# magnets.net
KiCad netlist of a schematic drawn in Altium Designer
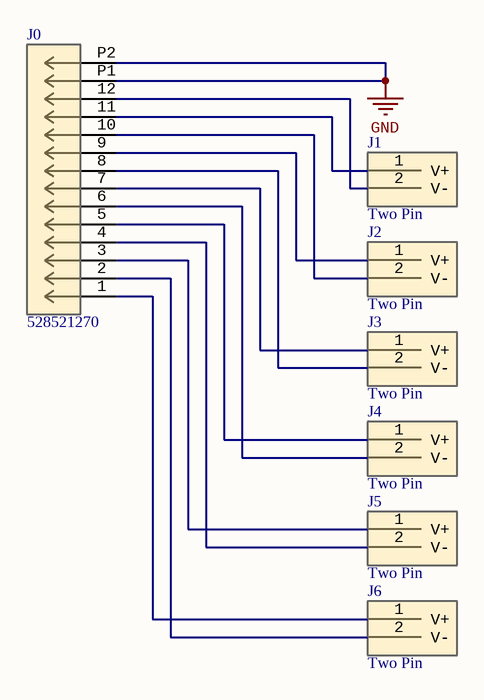
[diagram p0: magnets.SchDoc]

(export (version "E")
  (design (tool "Eeschema 10.0.6"))
  (components
    (comp (ref "J0")
      (value "528521270")
      (footprint "528521270:528521270")
      (fields (field (name "COPYRIGHT") "Copyright (C) 2025 Ultra Librarian. All rights reserved."))
      (libsource (lib "528521270") (part "528521270"))
    )
    (comp (ref "J1")
      (value "Two Pin")
      (footprint "twopin:TWO_PIN")
      (libsource (lib "twopin") (part "two_pin"))
    )
    (comp (ref "J2")
      (value "Two Pin")
      (footprint "twopin:TWO_PIN")
      (libsource (lib "twopin") (part "two_pin"))
    )
    (comp (ref "J3")
      (value "Two Pin")
      (footprint "twopin:TWO_PIN")
      (libsource (lib "twopin") (part "two_pin"))
    )
    (comp (ref "J4")
      (value "Two Pin")
      (footprint "twopin:TWO_PIN")
      (libsource (lib "twopin") (part "two_pin"))
    )
    (comp (ref "J5")
      (value "Two Pin")
      (footprint "twopin:TWO_PIN")
      (libsource (lib "twopin") (part "two_pin"))
    )
    (comp (ref "J6")
      (value "Two Pin")
      (footprint "twopin:TWO_PIN")
      (libsource (lib "twopin") (part "two_pin"))
    )
  )
  (nets
    (net (code "1") (name "GND") (class "Default")
      (node (ref "J0") (pin "P1") (pinfunction "P1_P1") (pintype "passive"))
      (node (ref "J0") (pin "P2") (pinfunction "P2_P2") (pintype "passive"))
    )
    (net (code "2") (name "Net-(J1-V+)") (class "Default")
      (node (ref "J0") (pin "11") (pinfunction "11_11") (pintype "passive"))
      (node (ref "J1") (pin "1") (pinfunction "V+_1") (pintype "passive"))
    )
    (net (code "3") (name "Net-(J1-V-)") (class "Default")
      (node (ref "J0") (pin "12") (pinfunction "12_12") (pintype "passive"))
      (node (ref "J1") (pin "2") (pinfunction "V-_2") (pintype "passive"))
    )
    (net (code "4") (name "Net-(J2-V+)") (class "Default")
      (node (ref "J0") (pin "9") (pinfunction "9_9") (pintype "passive"))
      (node (ref "J2") (pin "1") (pinfunction "V+_1") (pintype "passive"))
    )
    (net (code "5") (name "Net-(J2-V-)") (class "Default")
      (node (ref "J0") (pin "10") (pinfunction "10_10") (pintype "passive"))
      (node (ref "J2") (pin "2") (pinfunction "V-_2") (pintype "passive"))
    )
    (net (code "6") (name "Net-(J3-V+)") (class "Default")
      (node (ref "J0") (pin "7") (pinfunction "7_7") (pintype "passive"))
      (node (ref "J3") (pin "1") (pinfunction "V+_1") (pintype "passive"))
    )
    (net (code "7") (name "Net-(J3-V-)") (class "Default")
      (node (ref "J0") (pin "8") (pinfunction "8_8") (pintype "passive"))
      (node (ref "J3") (pin "2") (pinfunction "V-_2") (pintype "passive"))
    )
    (net (code "8") (name "Net-(J4-V+)") (class "Default")
      (node (ref "J0") (pin "5") (pinfunction "5_5") (pintype "passive"))
      (node (ref "J4") (pin "1") (pinfunction "V+_1") (pintype "passive"))
    )
    (net (code "9") (name "Net-(J4-V-)") (class "Default")
      (node (ref "J0") (pin "6") (pinfunction "6_6") (pintype "passive"))
      (node (ref "J4") (pin "2") (pinfunction "V-_2") (pintype "passive"))
    )
    (net (code "10") (name "Net-(J5-V+)") (class "Default")
      (node (ref "J0") (pin "3") (pinfunction "3_3") (pintype "passive"))
      (node (ref "J5") (pin "1") (pinfunction "V+_1") (pintype "passive"))
    )
    (net (code "11") (name "Net-(J5-V-)") (class "Default")
      (node (ref "J0") (pin "4") (pinfunction "4_4") (pintype "passive"))
      (node (ref "J5") (pin "2") (pinfunction "V-_2") (pintype "passive"))
    )
    (net (code "12") (name "Net-(J6-V+)") (class "Default")
      (node (ref "J0") (pin "1") (pinfunction "1_1") (pintype "passive"))
      (node (ref "J6") (pin "1") (pinfunction "V+_1") (pintype "passive"))
    )
    (net (code "13") (name "Net-(J6-V-)") (class "Default")
      (node (ref "J0") (pin "2") (pinfunction "2_2") (pintype "passive"))
      (node (ref "J6") (pin "2") (pinfunction "V-_2") (pintype "passive"))
    )
  )
)
